# miky-helloEcho.net
KiCad netlist of a schematic drawn in EAGLE
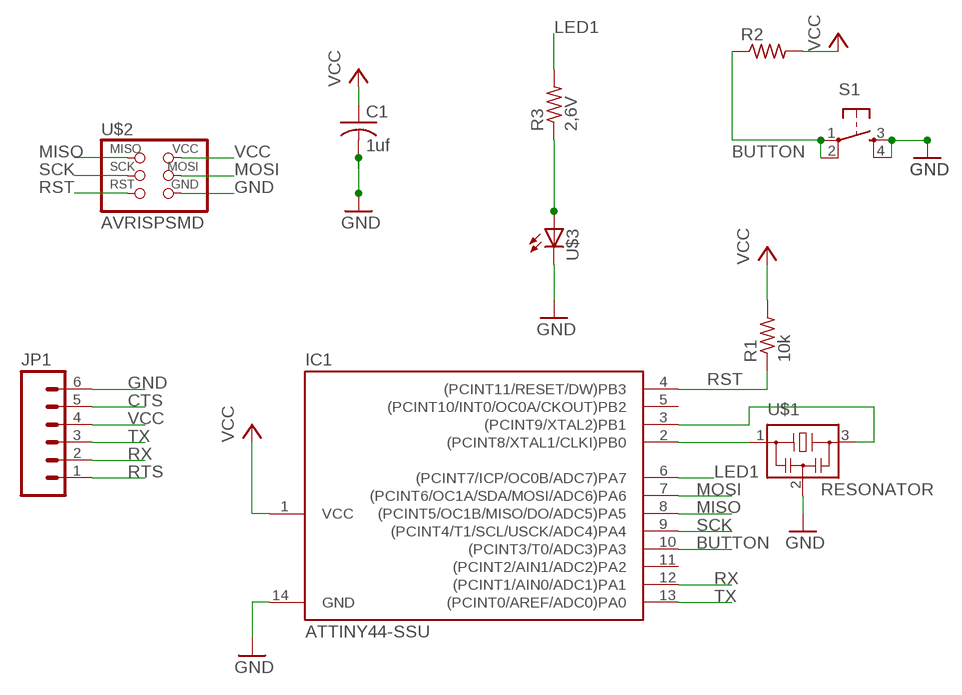
[diagram p0: schematic, sheet 1]

(export (version "E")
  (design (tool "Eeschema 10.0.6"))
  (components
    (comp (ref "C1")
      (value "1uf")
      (footprint "eagle-import:C1206")
      (libsource (lib "eagle-import") (part "C-USC1206"))
    )
    (comp (ref "IC1")
      (value "ATTINY44-SSU")
      (footprint "eagle-import:SOIC14")
      (libsource (lib "eagle-import") (part "ATTINY44-SSU"))
    )
    (comp (ref "JP1")
      (value "M06SMD")
      (footprint "eagle-import:1X06-SMD")
      (libsource (lib "eagle-import") (part "M06SMD"))
    )
    (comp (ref "R1")
      (value "10k")
      (footprint "eagle-import:R1206")
      (libsource (lib "eagle-import") (part "R-US_R1206"))
    )
    (comp (ref "R2")
      (value "RESISTOR1206")
      (footprint "eagle-import:1206")
      (libsource (lib "eagle-import") (part "RESISTOR1206"))
    )
    (comp (ref "R3")
      (value "2,6V")
      (footprint "eagle-import:R1206")
      (libsource (lib "eagle-import") (part "R-US_R1206"))
    )
    (comp (ref "S1")
      (value "6MM_SWITCH6MM_SWITCH")
      (footprint "eagle-import:6MM_SWITCH")
      (libsource (lib "eagle-import") (part "6MM_SWITCH6MM_SWITCH"))
    )
    (comp (ref "U$1")
      (value "RESONATOR")
      (footprint "eagle-import:EFOBM")
      (libsource (lib "eagle-import") (part "RESONATOR"))
    )
    (comp (ref "U$2")
      (value "AVRISPSMD")
      (footprint "eagle-import:2X03SMD")
      (libsource (lib "eagle-import") (part "AVRISPSMD"))
    )
    (comp (ref "U$3")
      (value "LED1206")
      (footprint "eagle-import:1206")
      (libsource (lib "eagle-import") (part "LED1206"))
    )
  )
  (nets
    (net (code "1") (name "/BUTTON") (class "Default")
      (node (ref "IC1") (pin "10") (pinfunction "(PCINT3/T0/ADC3)PA3_10") (pintype "bidirectional"))
      (node (ref "R2") (pin "1") (pinfunction "1_1") (pintype "passive"))
      (node (ref "S1") (pin "1") (pinfunction "P_1") (pintype "passive"))
      (node (ref "S1") (pin "2") (pinfunction "P1_2") (pintype "passive"))
    )
    (net (code "2") (name "/CTS") (class "Default")
      (node (ref "JP1") (pin "5") (pinfunction "5_5") (pintype "passive"))
    )
    (net (code "3") (name "/LED1") (class "Default")
      (node (ref "IC1") (pin "6") (pinfunction "(PCINT7/ICP/OC0B/ADC7)PA7_6") (pintype "bidirectional"))
      (node (ref "R3") (pin "2") (pinfunction "2_2") (pintype "passive"))
    )
    (net (code "4") (name "/MISO") (class "Default")
      (node (ref "IC1") (pin "8") (pinfunction "(PCINT5/OC1B/MISO/DO/ADC5)PA5_8") (pintype "bidirectional"))
      (node (ref "U$2") (pin "1") (pinfunction "MISO_1") (pintype "passive"))
    )
    (net (code "5") (name "/MOSI") (class "Default")
      (node (ref "IC1") (pin "7") (pinfunction "(PCINT6/OC1A/SDA/MOSI/ADC6)PA6_7") (pintype "bidirectional"))
      (node (ref "U$2") (pin "4") (pinfunction "MOSI_4") (pintype "passive"))
    )
    (net (code "6") (name "/RST") (class "Default")
      (node (ref "IC1") (pin "4") (pinfunction "(PCINT11/RESET/DW)PB3_4") (pintype "bidirectional"))
      (node (ref "R1") (pin "1") (pinfunction "1_1") (pintype "passive"))
      (node (ref "U$2") (pin "5") (pinfunction "RST_5") (pintype "passive"))
    )
    (net (code "7") (name "/RTS") (class "Default")
      (node (ref "JP1") (pin "1") (pinfunction "1_1") (pintype "passive"))
    )
    (net (code "8") (name "/RX") (class "Default")
      (node (ref "IC1") (pin "12") (pinfunction "(PCINT1/AIN0/ADC1)PA1_12") (pintype "bidirectional"))
      (node (ref "JP1") (pin "2") (pinfunction "2_2") (pintype "passive"))
    )
    (net (code "9") (name "/SCK") (class "Default")
      (node (ref "IC1") (pin "9") (pinfunction "(PCINT4/T1/SCL/USCK/ADC4)PA4_9") (pintype "bidirectional"))
      (node (ref "U$2") (pin "3") (pinfunction "SCK_3") (pintype "passive"))
    )
    (net (code "10") (name "/TX") (class "Default")
      (node (ref "IC1") (pin "13") (pinfunction "(PCINT0/AREF/ADC0)PA0_13") (pintype "bidirectional"))
      (node (ref "JP1") (pin "3") (pinfunction "3_3") (pintype "passive"))
    )
    (net (code "11") (name "GND") (class "Default")
      (node (ref "C1") (pin "2") (pinfunction "2_2") (pintype "passive"))
      (node (ref "IC1") (pin "14") (pinfunction "GND_14") (pintype "power_in"))
      (node (ref "JP1") (pin "6") (pinfunction "6_6") (pintype "passive"))
      (node (ref "S1") (pin "3") (pinfunction "S_3") (pintype "passive"))
      (node (ref "S1") (pin "4") (pinfunction "S1_4") (pintype "passive"))
      (node (ref "U$1") (pin "2") (pinfunction "2_2") (pintype "passive"))
      (node (ref "U$2") (pin "6") (pinfunction "GND_6") (pintype "passive"))
      (node (ref "U$3") (pin "2") (pinfunction "C_2") (pintype "passive"))
    )
    (net (code "12") (name "Net-(IC1-(PCINT8{slash}XTAL1{slash}CLKI)PB0)") (class "Default")
      (node (ref "IC1") (pin "2") (pinfunction "(PCINT8/XTAL1/CLKI)PB0_2") (pintype "bidirectional"))
      (node (ref "U$1") (pin "1") (pinfunction "1_1") (pintype "passive"))
    )
    (net (code "13") (name "Net-(IC1-(PCINT9{slash}XTAL2)PB1)") (class "Default")
      (node (ref "IC1") (pin "3") (pinfunction "(PCINT9/XTAL2)PB1_3") (pintype "bidirectional"))
      (node (ref "U$1") (pin "3") (pinfunction "3_3") (pintype "passive"))
    )
    (net (code "14") (name "Net-(U$3-A)") (class "Default")
      (node (ref "R3") (pin "1") (pinfunction "1_1") (pintype "passive"))
      (node (ref "U$3") (pin "1") (pinfunction "A_1") (pintype "passive"))
    )
    (net (code "15") (name "VCC") (class "Default")
      (node (ref "C1") (pin "1") (pinfunction "1_1") (pintype "passive"))
      (node (ref "IC1") (pin "1") (pinfunction "VCC_1") (pintype "power_in"))
      (node (ref "JP1") (pin "4") (pinfunction "4_4") (pintype "passive"))
      (node (ref "R1") (pin "2") (pinfunction "2_2") (pintype "passive"))
      (node (ref "R2") (pin "2") (pinfunction "2_2") (pintype "passive"))
      (node (ref "U$2") (pin "2") (pinfunction "VCC_2") (pintype "passive"))
    )
    (net (code "16") (name "unconnected-(IC1-(PCINT2{slash}AIN1{slash}ADC2)PA2-Pad11)") (class "Default")
      (node (ref "IC1") (pin "11") (pinfunction "(PCINT2/AIN1/ADC2)PA2_11") (pintype "bidirectional"))
    )
    (net (code "17") (name "unconnected-(IC1-(PCINT10{slash}INT0{slash}OC0A{slash}CKOUT)PB2-Pad5)") (class "Default")
      (node (ref "IC1") (pin "5") (pinfunction "(PCINT10/INT0/OC0A/CKOUT)PB2_5") (pintype "bidirectional"))
    )
  )
)
